# components.net
KiCad netlist of a schematic drawn in EAGLE
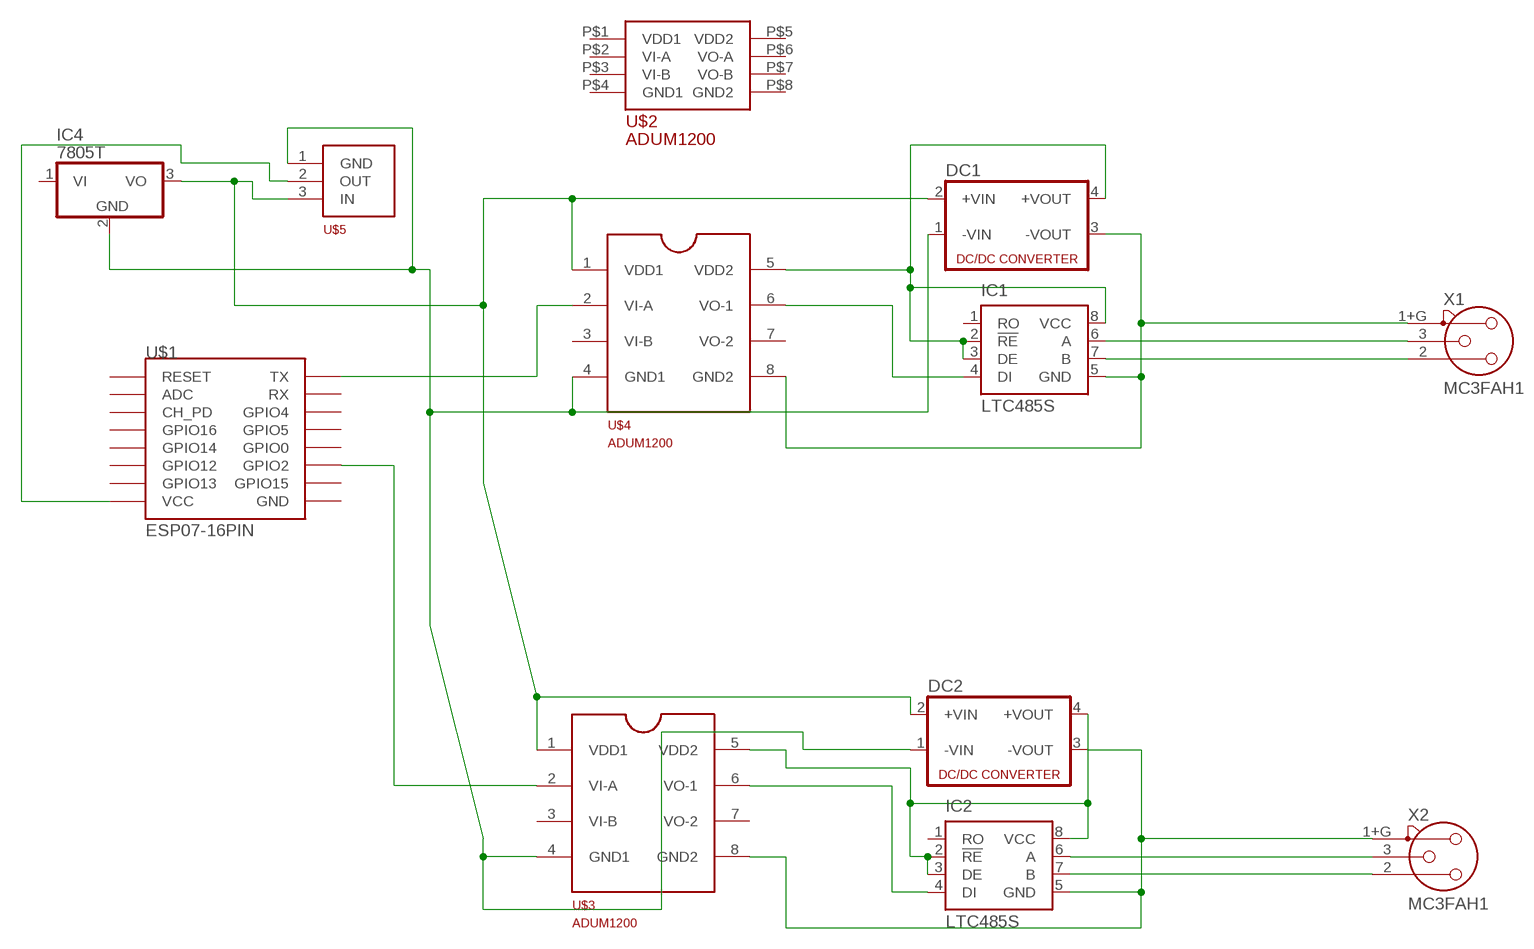
[diagram p0: schematic, sheet 1]

(export (version "E")
  (design (tool "Eeschema 10.0.6"))
  (components
    (comp (ref "DC1")
      (value "NME")
      (footprint "eagle-import:NME")
      (fields (field (name "MF") "C & D TECHNOLOGIES, INC") (field (name "MPN") "NME1205D"))
      (libsource (lib "eagle-import") (part "NME"))
    )
    (comp (ref "DC2")
      (value "NME")
      (footprint "eagle-import:NME")
      (fields (field (name "MF") "C & D TECHNOLOGIES, INC") (field (name "MPN") "NME1205D"))
      (libsource (lib "eagle-import") (part "NME"))
    )
    (comp (ref "IC1")
      (value "LTC485S")
      (footprint "eagle-import:SOIC8")
      (libsource (lib "eagle-import") (part "LTC485S"))
    )
    (comp (ref "IC2")
      (value "LTC485S")
      (footprint "eagle-import:SOIC8")
      (libsource (lib "eagle-import") (part "LTC485S"))
    )
    (comp (ref "IC4")
      (value "7805T")
      (footprint "eagle-import:TO220H")
      (libsource (lib "eagle-import") (part "78T05"))
    )
    (comp (ref "U$1")
      (value "ESP07-16PIN")
      (footprint "eagle-import:ESP07-16PIN")
      (libsource (lib "eagle-import") (part "ESP07-16PIN"))
    )
    (comp (ref "U$2")
      (value "ADUM1200SO8")
      (footprint "eagle-import:SO8")
      (libsource (lib "eagle-import") (part "ADUM1200SO8"))
    )
    (comp (ref "U$3")
      (value "ADUM1200")
      (footprint "eagle-import:SO8")
      (libsource (lib "eagle-import") (part "ADUM1200"))
    )
    (comp (ref "U$4")
      (value "ADUM1200")
      (footprint "eagle-import:SO8")
      (libsource (lib "eagle-import") (part "ADUM1200"))
    )
    (comp (ref "U$5")
      (value "AMS1117")
      (footprint "eagle-import:SOT223")
      (libsource (lib "eagle-import") (part "AMS1117"))
    )
    (comp (ref "X1")
      (value "MC3FAH1")
      (footprint "eagle-import:NC3FAH1")
      (libsource (lib "eagle-import") (part "MC3?FAH1"))
    )
    (comp (ref "X2")
      (value "MC3FAH1")
      (footprint "eagle-import:NC3FAH1")
      (libsource (lib "eagle-import") (part "MC3?FAH1"))
    )
  )
  (nets
    (net (code "1") (name "Net-(DC1-+VIN)") (class "Default")
      (node (ref "DC1") (pin "2") (pinfunction "+VIN_2") (pintype "passive"))
      (node (ref "DC2") (pin "2") (pinfunction "+VIN_2") (pintype "passive"))
      (node (ref "IC4") (pin "3") (pinfunction "VO_3") (pintype "passive"))
      (node (ref "U$3") (pin "1") (pinfunction "VDD1_1") (pintype "bidirectional"))
      (node (ref "U$4") (pin "1") (pinfunction "VDD1_1") (pintype "bidirectional"))
      (node (ref "U$5") (pin "3") (pinfunction "IN_3") (pintype "bidirectional"))
    )
    (net (code "2") (name "Net-(DC1-+VOUT)") (class "Default")
      (node (ref "DC1") (pin "4") (pinfunction "+VOUT_4") (pintype "passive"))
      (node (ref "IC1") (pin "2") (pinfunction "~{RE}_2") (pintype "input"))
      (node (ref "IC1") (pin "3") (pinfunction "DE_3") (pintype "input"))
      (node (ref "IC1") (pin "8") (pinfunction "VCC_8") (pintype "input"))
      (node (ref "U$4") (pin "5") (pinfunction "VDD2_5") (pintype "bidirectional"))
    )
    (net (code "3") (name "Net-(DC1--VIN)") (class "Default")
      (node (ref "DC1") (pin "1") (pinfunction "-VIN_1") (pintype "passive"))
      (node (ref "DC2") (pin "1") (pinfunction "-VIN_1") (pintype "passive"))
      (node (ref "IC4") (pin "2") (pinfunction "GND_2") (pintype "passive"))
      (node (ref "U$3") (pin "4") (pinfunction "GND1_4") (pintype "bidirectional"))
      (node (ref "U$4") (pin "4") (pinfunction "GND1_4") (pintype "bidirectional"))
      (node (ref "U$5") (pin "1") (pinfunction "GND_1") (pintype "bidirectional"))
    )
    (net (code "4") (name "Net-(DC1--VOUT)") (class "Default")
      (node (ref "DC1") (pin "3") (pinfunction "-VOUT_3") (pintype "passive"))
      (node (ref "IC1") (pin "5") (pinfunction "GND_5") (pintype "input"))
      (node (ref "U$4") (pin "8") (pinfunction "GND2_8") (pintype "bidirectional"))
      (node (ref "X1") (pin "1+G") (pinfunction "1_1+G") (pintype "passive"))
    )
    (net (code "5") (name "Net-(DC2-+VOUT)") (class "Default")
      (node (ref "DC2") (pin "4") (pinfunction "+VOUT_4") (pintype "passive"))
      (node (ref "IC2") (pin "2") (pinfunction "~{RE}_2") (pintype "input"))
      (node (ref "IC2") (pin "3") (pinfunction "DE_3") (pintype "input"))
      (node (ref "IC2") (pin "8") (pinfunction "VCC_8") (pintype "input"))
      (node (ref "U$3") (pin "5") (pinfunction "VDD2_5") (pintype "bidirectional"))
    )
    (net (code "6") (name "Net-(DC2--VOUT)") (class "Default")
      (node (ref "DC2") (pin "3") (pinfunction "-VOUT_3") (pintype "passive"))
      (node (ref "IC2") (pin "5") (pinfunction "GND_5") (pintype "input"))
      (node (ref "U$3") (pin "8") (pinfunction "GND2_8") (pintype "bidirectional"))
      (node (ref "X2") (pin "1+G") (pinfunction "1_1+G") (pintype "passive"))
    )
    (net (code "7") (name "Net-(IC1-A)") (class "Default")
      (node (ref "IC1") (pin "6") (pinfunction "A_6") (pintype "bidirectional"))
      (node (ref "X1") (pin "3") (pinfunction "3_3") (pintype "passive"))
    )
    (net (code "8") (name "Net-(IC1-B)") (class "Default")
      (node (ref "IC1") (pin "7") (pinfunction "B_7") (pintype "bidirectional"))
      (node (ref "X1") (pin "2") (pinfunction "2_2") (pintype "passive"))
    )
    (net (code "9") (name "Net-(IC1-DI)") (class "Default")
      (node (ref "IC1") (pin "4") (pinfunction "DI_4") (pintype "input"))
      (node (ref "U$4") (pin "6") (pinfunction "VO-1_6") (pintype "bidirectional"))
    )
    (net (code "10") (name "Net-(IC2-A)") (class "Default")
      (node (ref "IC2") (pin "6") (pinfunction "A_6") (pintype "bidirectional"))
      (node (ref "X2") (pin "3") (pinfunction "3_3") (pintype "passive"))
    )
    (net (code "11") (name "Net-(IC2-B)") (class "Default")
      (node (ref "IC2") (pin "7") (pinfunction "B_7") (pintype "bidirectional"))
      (node (ref "X2") (pin "2") (pinfunction "2_2") (pintype "passive"))
    )
    (net (code "12") (name "Net-(IC2-DI)") (class "Default")
      (node (ref "IC2") (pin "4") (pinfunction "DI_4") (pintype "input"))
      (node (ref "U$3") (pin "6") (pinfunction "VO-1_6") (pintype "bidirectional"))
    )
    (net (code "13") (name "Net-(U$3-VI-A)") (class "Default")
      (node (ref "U$1") (pin "GPIO2") (pinfunction "GPIO2_GPIO2") (pintype "bidirectional"))
      (node (ref "U$3") (pin "2") (pinfunction "VI-A_2") (pintype "bidirectional"))
    )
    (net (code "14") (name "Net-(U$4-VI-A)") (class "Default")
      (node (ref "U$1") (pin "TX") (pinfunction "TX_TX") (pintype "bidirectional"))
      (node (ref "U$4") (pin "2") (pinfunction "VI-A_2") (pintype "bidirectional"))
    )
    (net (code "15") (name "Net-(U$5-OUT)") (class "Default")
      (node (ref "U$1") (pin "VCC") (pinfunction "VCC_VCC") (pintype "bidirectional"))
      (node (ref "U$5") (pin "2") (pinfunction "OUT_2") (pintype "bidirectional"))
    )
    (net (code "16") (name "unconnected-(IC1-RO-Pad1)") (class "Default")
      (node (ref "IC1") (pin "1") (pinfunction "RO_1") (pintype "output"))
    )
    (net (code "17") (name "unconnected-(IC2-RO-Pad1)") (class "Default")
      (node (ref "IC2") (pin "1") (pinfunction "RO_1") (pintype "output"))
    )
    (net (code "18") (name "unconnected-(IC4-VI-Pad1)") (class "Default")
      (node (ref "IC4") (pin "1") (pinfunction "VI_1") (pintype "input"))
    )
    (net (code "19") (name "unconnected-(U$1-PadADC)") (class "Default")
      (node (ref "U$1") (pin "ADC") (pinfunction "ADC_ADC") (pintype "bidirectional"))
    )
    (net (code "20") (name "unconnected-(U$1-PadCH_PD)") (class "Default")
      (node (ref "U$1") (pin "CH_PD") (pinfunction "CH_PD_CH_PD") (pintype "bidirectional"))
    )
    (net (code "21") (name "unconnected-(U$1-PadGND)") (class "Default")
      (node (ref "U$1") (pin "GND") (pinfunction "GND_GND") (pintype "bidirectional"))
    )
    (net (code "22") (name "unconnected-(U$1-PadGPIO0)") (class "Default")
      (node (ref "U$1") (pin "GPIO0") (pinfunction "GPIO0_GPIO0") (pintype "bidirectional"))
    )
    (net (code "23") (name "unconnected-(U$1-PadGPIO4)") (class "Default")
      (node (ref "U$1") (pin "GPIO4") (pinfunction "GPIO4_GPIO4") (pintype "bidirectional"))
    )
    (net (code "24") (name "unconnected-(U$1-PadGPIO5)") (class "Default")
      (node (ref "U$1") (pin "GPIO5") (pinfunction "GPIO5_GPIO5") (pintype "bidirectional"))
    )
    (net (code "25") (name "unconnected-(U$1-PadGPIO12)") (class "Default")
      (node (ref "U$1") (pin "GPIO12") (pinfunction "GPIO12_GPIO12") (pintype "bidirectional"))
    )
    (net (code "26") (name "unconnected-(U$1-PadGPIO13)") (class "Default")
      (node (ref "U$1") (pin "GPIO13") (pinfunction "GPIO13_GPIO13") (pintype "bidirectional"))
    )
    (net (code "27") (name "unconnected-(U$1-PadGPIO14)") (class "Default")
      (node (ref "U$1") (pin "GPIO14") (pinfunction "GPIO14_GPIO14") (pintype "bidirectional"))
    )
    (net (code "28") (name "unconnected-(U$1-PadGPIO15)") (class "Default")
      (node (ref "U$1") (pin "GPIO15") (pinfunction "GPIO15_GPIO15") (pintype "bidirectional"))
    )
    (net (code "29") (name "unconnected-(U$1-PadGPIO16)") (class "Default")
      (node (ref "U$1") (pin "GPIO16") (pinfunction "GPIO16_GPIO16") (pintype "bidirectional"))
    )
    (net (code "30") (name "unconnected-(U$1-PadRX)") (class "Default")
      (node (ref "U$1") (pin "RX") (pinfunction "RX_RX") (pintype "bidirectional"))
    )
    (net (code "31") (name "unconnected-(U$1-RESET-PadREST)") (class "Default")
      (node (ref "U$1") (pin "REST") (pinfunction "RESET_REST") (pintype "bidirectional"))
    )
    (net (code "32") (name "unconnected-(U$2-GND1-PadP$4)") (class "Default")
      (node (ref "U$2") (pin "P$4") (pinfunction "GND1_P$4") (pintype "bidirectional"))
    )
    (net (code "33") (name "unconnected-(U$2-GND2-PadP$8)") (class "Default")
      (node (ref "U$2") (pin "P$8") (pinfunction "GND2_P$8") (pintype "bidirectional"))
    )
    (net (code "34") (name "unconnected-(U$2-VDD1-PadP$1)") (class "Default")
      (node (ref "U$2") (pin "P$1") (pinfunction "VDD1_P$1") (pintype "bidirectional"))
    )
    (net (code "35") (name "unconnected-(U$2-VDD2-PadP$5)") (class "Default")
      (node (ref "U$2") (pin "P$5") (pinfunction "VDD2_P$5") (pintype "bidirectional"))
    )
    (net (code "36") (name "unconnected-(U$2-VI-A-PadP$2)") (class "Default")
      (node (ref "U$2") (pin "P$2") (pinfunction "VI-A_P$2") (pintype "bidirectional"))
    )
    (net (code "37") (name "unconnected-(U$2-VI-B-PadP$3)") (class "Default")
      (node (ref "U$2") (pin "P$3") (pinfunction "VI-B_P$3") (pintype "bidirectional"))
    )
    (net (code "38") (name "unconnected-(U$2-VO-A-PadP$6)") (class "Default")
      (node (ref "U$2") (pin "P$6") (pinfunction "VO-A_P$6") (pintype "bidirectional"))
    )
    (net (code "39") (name "unconnected-(U$2-VO-B-PadP$7)") (class "Default")
      (node (ref "U$2") (pin "P$7") (pinfunction "VO-B_P$7") (pintype "bidirectional"))
    )
    (net (code "40") (name "unconnected-(U$3-VI-B-Pad3)") (class "Default")
      (node (ref "U$3") (pin "3") (pinfunction "VI-B_3") (pintype "bidirectional"))
    )
    (net (code "41") (name "unconnected-(U$3-VO-2-Pad7)") (class "Default")
      (node (ref "U$3") (pin "7") (pinfunction "VO-2_7") (pintype "bidirectional"))
    )
    (net (code "42") (name "unconnected-(U$4-VI-B-Pad3)") (class "Default")
      (node (ref "U$4") (pin "3") (pinfunction "VI-B_3") (pintype "bidirectional"))
    )
    (net (code "43") (name "unconnected-(U$4-VO-2-Pad7)") (class "Default")
      (node (ref "U$4") (pin "7") (pinfunction "VO-2_7") (pintype "bidirectional"))
    )
  )
)
